# DE-130418.net
KiCad netlist of a schematic drawn in Altium Designer
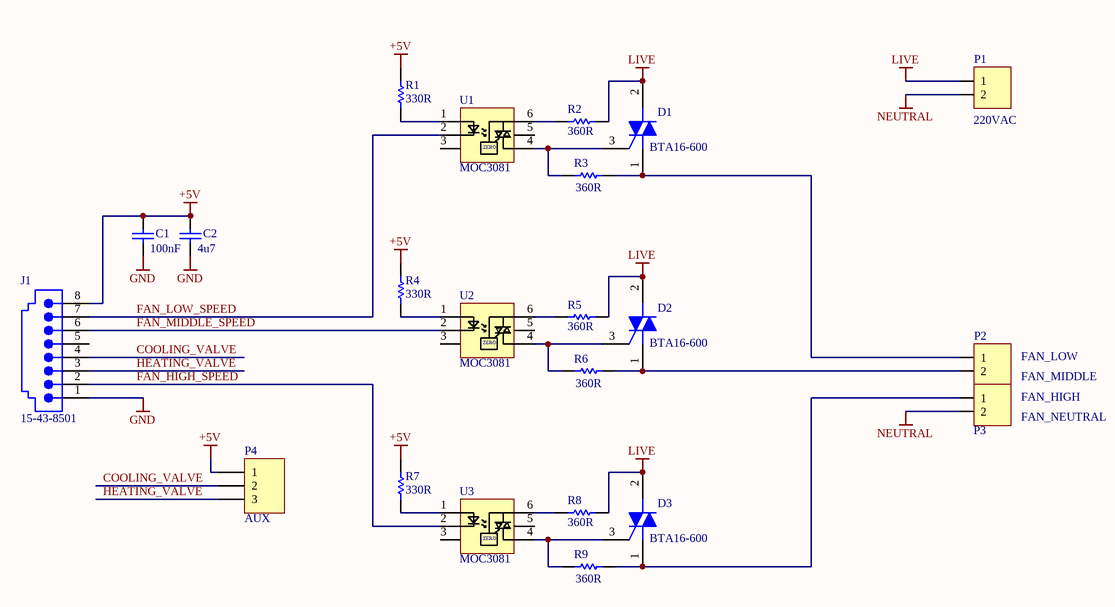
[diagram p0: DE-130418.SchDoc]

(export (version "E")
  (design (tool "Eeschema 10.0.6"))
  (components
    (comp (ref "C1")
      (value "100nF")
      (footprint "0603")
      (description "Ceramic Chip Capacitor - Standard")
      (fields (field (name "PUBLISHER") "Altium Limited"))
      (libsource (lib "DE-130418") (part "C0603"))
    )
    (comp (ref "C2")
      (value "4u7")
      (footprint "0805")
      (description "Ceramic Chip Capacitor - Standard")
      (fields (field (name "PUBLISHER") "Altium Limited"))
      (libsource (lib "DE-130418") (part "C0805"))
    )
    (comp (ref "D1")
      (value "BTA16-600")
      (footprint "ONSC-TO-220-3-221A-07")
      (description "Triacs, Silicon Bidirectional Thyristor, 3-Pin TO-220, Pb-Free, Tube")
      (fields (field (name "MANUFACTURER") "On Semiconductor") (field (name "PARTNUMBER") "BTA08-600BW3G"))
      (libsource (lib "DE-130418") (part "BTA08-600BW3G"))
    )
    (comp (ref "D2")
      (value "BTA16-600")
      (footprint "ONSC-TO-220-3-221A-07")
      (description "Triacs, Silicon Bidirectional Thyristor, 3-Pin TO-220, Pb-Free, Tube")
      (fields (field (name "MANUFACTURER") "On Semiconductor") (field (name "PARTNUMBER") "BTA08-600BW3G"))
      (libsource (lib "DE-130418") (part "BTA08-600BW3G"))
    )
    (comp (ref "D3")
      (value "BTA16-600")
      (footprint "ONSC-TO-220-3-221A-07")
      (description "Triacs, Silicon Bidirectional Thyristor, 3-Pin TO-220, Pb-Free, Tube")
      (fields (field (name "MANUFACTURER") "On Semiconductor") (field (name "PARTNUMBER") "BTA08-600BW3G"))
      (libsource (lib "DE-130418") (part "BTA08-600BW3G"))
    )
    (comp (ref "J1")
      (value "15-43-8501")
      (footprint "15-43-8501")
      (description "Right Angle, Standard Profile, RJ-45 Keyed, Unshielded PCB Jack")
      (fields (field (name "PUBLISHER") "Altium Limited"))
      (libsource (lib "Molex Modular Jack Right Angle") (part "15-43-8501"))
    )
    (comp (ref "P1")
      (value "220VAC")
      (footprint "TERMINAL BLOK 2")
      (description "Terminal blok konektor 5 mm")
      (libsource (lib "DE-130418") (part "TERMINAL BLOK 2"))
    )
    (comp (ref "P2")
      (value "~")
      (footprint "TERMINAL BLOK 2")
      (description "Terminal blok konektor 5 mm")
      (libsource (lib "DE-130418") (part "TERMINAL BLOK 2"))
    )
    (comp (ref "P3")
      (value "~")
      (footprint "TERMINAL BLOK 2")
      (description "Terminal blok konektor 5 mm")
      (libsource (lib "DE-130418") (part "TERMINAL BLOK 2"))
    )
    (comp (ref "P4")
      (value "AUX")
      (footprint "HDR1X3")
      (description "Header, 3-Pin")
      (fields (field (name "PUBLISHER") "Altium Limited"))
      (libsource (lib "Miscellaneous Connectors") (part "Header 3"))
    )
    (comp (ref "R1")
      (value "330R")
      (footprint "ERA-0805")
      (fields (field (name "PUBLISHER") "Altium Limited"))
      (libsource (lib "DE-130418") (part "ERAS"))
    )
    (comp (ref "R2")
      (value "360R")
      (footprint "RD6.35x2.3")
      (description "Carbon Film Resistor, 1 Ohm to 3.3M Ohm Range, 5% Tolerance, 0.5 W")
      (fields (field (name "PUBLISHER") "Altium Limited"))
      (libsource (lib "DE-130418") (part "ERDS1T"))
    )
    (comp (ref "R3")
      (value "360R")
      (footprint "RD6.35x2.3")
      (description "Carbon Film Resistor, 1 Ohm to 3.3M Ohm Range, 5% Tolerance, 0.5 W")
      (fields (field (name "PUBLISHER") "Altium Limited"))
      (libsource (lib "DE-130418") (part "ERDS1T"))
    )
    (comp (ref "R4")
      (value "330R")
      (footprint "ERA-0805")
      (fields (field (name "PUBLISHER") "Altium Limited"))
      (libsource (lib "DE-130418") (part "ERAS"))
    )
    (comp (ref "R5")
      (value "360R")
      (footprint "RD6.35x2.3")
      (description "Carbon Film Resistor, 1 Ohm to 3.3M Ohm Range, 5% Tolerance, 0.5 W")
      (fields (field (name "PUBLISHER") "Altium Limited"))
      (libsource (lib "DE-130418") (part "ERDS1T"))
    )
    (comp (ref "R6")
      (value "360R")
      (footprint "RD6.35x2.3")
      (description "Carbon Film Resistor, 1 Ohm to 3.3M Ohm Range, 5% Tolerance, 0.5 W")
      (fields (field (name "PUBLISHER") "Altium Limited"))
      (libsource (lib "DE-130418") (part "ERDS1T"))
    )
    (comp (ref "R7")
      (value "330R")
      (footprint "ERA-0805")
      (fields (field (name "PUBLISHER") "Altium Limited"))
      (libsource (lib "DE-130418") (part "ERAS"))
    )
    (comp (ref "R8")
      (value "360R")
      (footprint "RD6.35x2.3")
      (description "Carbon Film Resistor, 1 Ohm to 3.3M Ohm Range, 5% Tolerance, 0.5 W")
      (fields (field (name "PUBLISHER") "Altium Limited"))
      (libsource (lib "DE-130418") (part "ERDS1T"))
    )
    (comp (ref "R9")
      (value "360R")
      (footprint "RD6.35x2.3")
      (description "Carbon Film Resistor, 1 Ohm to 3.3M Ohm Range, 5% Tolerance, 0.5 W")
      (fields (field (name "PUBLISHER") "Altium Limited"))
      (libsource (lib "DE-130418") (part "ERDS1T"))
    )
    (comp (ref "U1")
      (value "MOC3081")
      (footprint "DIP6")
      (description "Zero-Cross Optoisolator Triac Driver")
      (libsource (lib "DE-130418") (part "MOC3081"))
    )
    (comp (ref "U2")
      (value "MOC3081")
      (footprint "DIP6")
      (description "Zero-Cross Optoisolator Triac Driver")
      (libsource (lib "DE-130418") (part "MOC3081"))
    )
    (comp (ref "U3")
      (value "MOC3081")
      (footprint "DIP6")
      (description "Zero-Cross Optoisolator Triac Driver")
      (libsource (lib "DE-130418") (part "MOC3081"))
    )
  )
  (nets
    (net (code "1") (name "+5V") (class "Default")
      (node (ref "C1") (pin "2") (pinfunction "2_2") (pintype "passive"))
      (node (ref "C2") (pin "2") (pinfunction "2_2") (pintype "passive"))
      (node (ref "J1") (pin "8") (pinfunction "8_8") (pintype "passive"))
      (node (ref "P4") (pin "1") (pinfunction "1_1") (pintype "passive"))
      (node (ref "R1") (pin "2") (pinfunction "2_2") (pintype "passive"))
      (node (ref "R4") (pin "2") (pinfunction "2_2") (pintype "passive"))
      (node (ref "R7") (pin "2") (pinfunction "2_2") (pintype "passive"))
    )
    (net (code "2") (name "/COOLING_VALVE") (class "Default")
      (node (ref "J1") (pin "4") (pinfunction "4_4") (pintype "passive"))
      (node (ref "P4") (pin "2") (pinfunction "2_2") (pintype "passive"))
    )
    (net (code "3") (name "/FAN_HIGH_SPEED") (class "Default")
      (node (ref "J1") (pin "2") (pinfunction "2_2") (pintype "passive"))
      (node (ref "U3") (pin "2") (pinfunction "2_2") (pintype "passive"))
    )
    (net (code "4") (name "/FAN_LOW_SPEED") (class "Default")
      (node (ref "J1") (pin "7") (pinfunction "7_7") (pintype "passive"))
      (node (ref "U1") (pin "2") (pinfunction "2_2") (pintype "passive"))
    )
    (net (code "5") (name "/FAN_MIDDLE_SPEED") (class "Default")
      (node (ref "J1") (pin "6") (pinfunction "6_6") (pintype "passive"))
      (node (ref "U2") (pin "2") (pinfunction "2_2") (pintype "passive"))
    )
    (net (code "6") (name "/HEATING_VALVE") (class "Default")
      (node (ref "J1") (pin "3") (pinfunction "3_3") (pintype "passive"))
      (node (ref "P4") (pin "3") (pinfunction "3_3") (pintype "passive"))
    )
    (net (code "7") (name "GND") (class "Default")
      (node (ref "C1") (pin "1") (pinfunction "1_1") (pintype "passive"))
      (node (ref "C2") (pin "1") (pinfunction "1_1") (pintype "passive"))
      (node (ref "J1") (pin "1") (pinfunction "1_1") (pintype "passive"))
    )
    (net (code "8") (name "LIVE") (class "Default")
      (node (ref "D1") (pin "2") (pinfunction "MT2_2") (pintype "passive"))
      (node (ref "D2") (pin "2") (pinfunction "MT2_2") (pintype "passive"))
      (node (ref "D3") (pin "2") (pinfunction "MT2_2") (pintype "passive"))
      (node (ref "P1") (pin "1") (pinfunction "1_1") (pintype "passive"))
      (node (ref "R2") (pin "2") (pinfunction "2_2") (pintype "passive"))
      (node (ref "R5") (pin "2") (pinfunction "2_2") (pintype "passive"))
      (node (ref "R8") (pin "2") (pinfunction "2_2") (pintype "passive"))
    )
    (net (code "9") (name "NEUTRAL") (class "Default")
      (node (ref "P1") (pin "2") (pinfunction "2_2") (pintype "passive"))
      (node (ref "P3") (pin "2") (pinfunction "2_2") (pintype "passive"))
    )
    (net (code "10") (name "Net-(D1-G)") (class "Default")
      (node (ref "D1") (pin "3") (pinfunction "G_3") (pintype "passive"))
      (node (ref "R3") (pin "1") (pinfunction "1_1") (pintype "passive"))
      (node (ref "U1") (pin "4") (pinfunction "4_4") (pintype "passive"))
    )
    (net (code "11") (name "Net-(D1-MT1)") (class "Default")
      (node (ref "D1") (pin "1") (pinfunction "MT1_1") (pintype "passive"))
      (node (ref "P2") (pin "1") (pinfunction "1_1") (pintype "passive"))
      (node (ref "R3") (pin "2") (pinfunction "2_2") (pintype "passive"))
    )
    (net (code "12") (name "Net-(D2-G)") (class "Default")
      (node (ref "D2") (pin "3") (pinfunction "G_3") (pintype "passive"))
      (node (ref "R6") (pin "1") (pinfunction "1_1") (pintype "passive"))
      (node (ref "U2") (pin "4") (pinfunction "4_4") (pintype "passive"))
    )
    (net (code "13") (name "Net-(D2-MT1)") (class "Default")
      (node (ref "D2") (pin "1") (pinfunction "MT1_1") (pintype "passive"))
      (node (ref "P2") (pin "2") (pinfunction "2_2") (pintype "passive"))
      (node (ref "R6") (pin "2") (pinfunction "2_2") (pintype "passive"))
    )
    (net (code "14") (name "Net-(D3-G)") (class "Default")
      (node (ref "D3") (pin "3") (pinfunction "G_3") (pintype "passive"))
      (node (ref "R9") (pin "1") (pinfunction "1_1") (pintype "passive"))
      (node (ref "U3") (pin "4") (pinfunction "4_4") (pintype "passive"))
    )
    (net (code "15") (name "Net-(D3-MT1)") (class "Default")
      (node (ref "D3") (pin "1") (pinfunction "MT1_1") (pintype "passive"))
      (node (ref "P3") (pin "1") (pinfunction "1_1") (pintype "passive"))
      (node (ref "R9") (pin "2") (pinfunction "2_2") (pintype "passive"))
    )
    (net (code "16") (name "Net-(R1-Pad1)") (class "Default")
      (node (ref "R1") (pin "1") (pinfunction "1_1") (pintype "passive"))
      (node (ref "U1") (pin "1") (pinfunction "1_1") (pintype "passive"))
    )
    (net (code "17") (name "Net-(R2-Pad1)") (class "Default")
      (node (ref "R2") (pin "1") (pinfunction "1_1") (pintype "passive"))
      (node (ref "U1") (pin "6") (pinfunction "6_6") (pintype "passive"))
    )
    (net (code "18") (name "Net-(R4-Pad1)") (class "Default")
      (node (ref "R4") (pin "1") (pinfunction "1_1") (pintype "passive"))
      (node (ref "U2") (pin "1") (pinfunction "1_1") (pintype "passive"))
    )
    (net (code "19") (name "Net-(R5-Pad1)") (class "Default")
      (node (ref "R5") (pin "1") (pinfunction "1_1") (pintype "passive"))
      (node (ref "U2") (pin "6") (pinfunction "6_6") (pintype "passive"))
    )
    (net (code "20") (name "Net-(R7-Pad1)") (class "Default")
      (node (ref "R7") (pin "1") (pinfunction "1_1") (pintype "passive"))
      (node (ref "U3") (pin "1") (pinfunction "1_1") (pintype "passive"))
    )
    (net (code "21") (name "Net-(R8-Pad1)") (class "Default")
      (node (ref "R8") (pin "1") (pinfunction "1_1") (pintype "passive"))
      (node (ref "U3") (pin "6") (pinfunction "6_6") (pintype "passive"))
    )
    (net (code "22") (name "unconnected-(J1-Pad5)") (class "Default")
      (node (ref "J1") (pin "5") (pinfunction "5_5") (pintype "passive"))
    )
    (net (code "23") (name "unconnected-(U1-Pad3)") (class "Default")
      (node (ref "U1") (pin "3") (pinfunction "3_3") (pintype "passive"))
    )
    (net (code "24") (name "unconnected-(U1-Pad5)") (class "Default")
      (node (ref "U1") (pin "5") (pinfunction "5_5") (pintype "passive"))
    )
    (net (code "25") (name "unconnected-(U2-Pad3)") (class "Default")
      (node (ref "U2") (pin "3") (pinfunction "3_3") (pintype "passive"))
    )
    (net (code "26") (name "unconnected-(U2-Pad5)") (class "Default")
      (node (ref "U2") (pin "5") (pinfunction "5_5") (pintype "passive"))
    )
    (net (code "27") (name "unconnected-(U3-Pad3)") (class "Default")
      (node (ref "U3") (pin "3") (pinfunction "3_3") (pintype "passive"))
    )
    (net (code "28") (name "unconnected-(U3-Pad5)") (class "Default")
      (node (ref "U3") (pin "5") (pinfunction "5_5") (pintype "passive"))
    )
  )
)
